# MIPI_Panel.net
KiCad netlist of a schematic drawn in Altium Designer
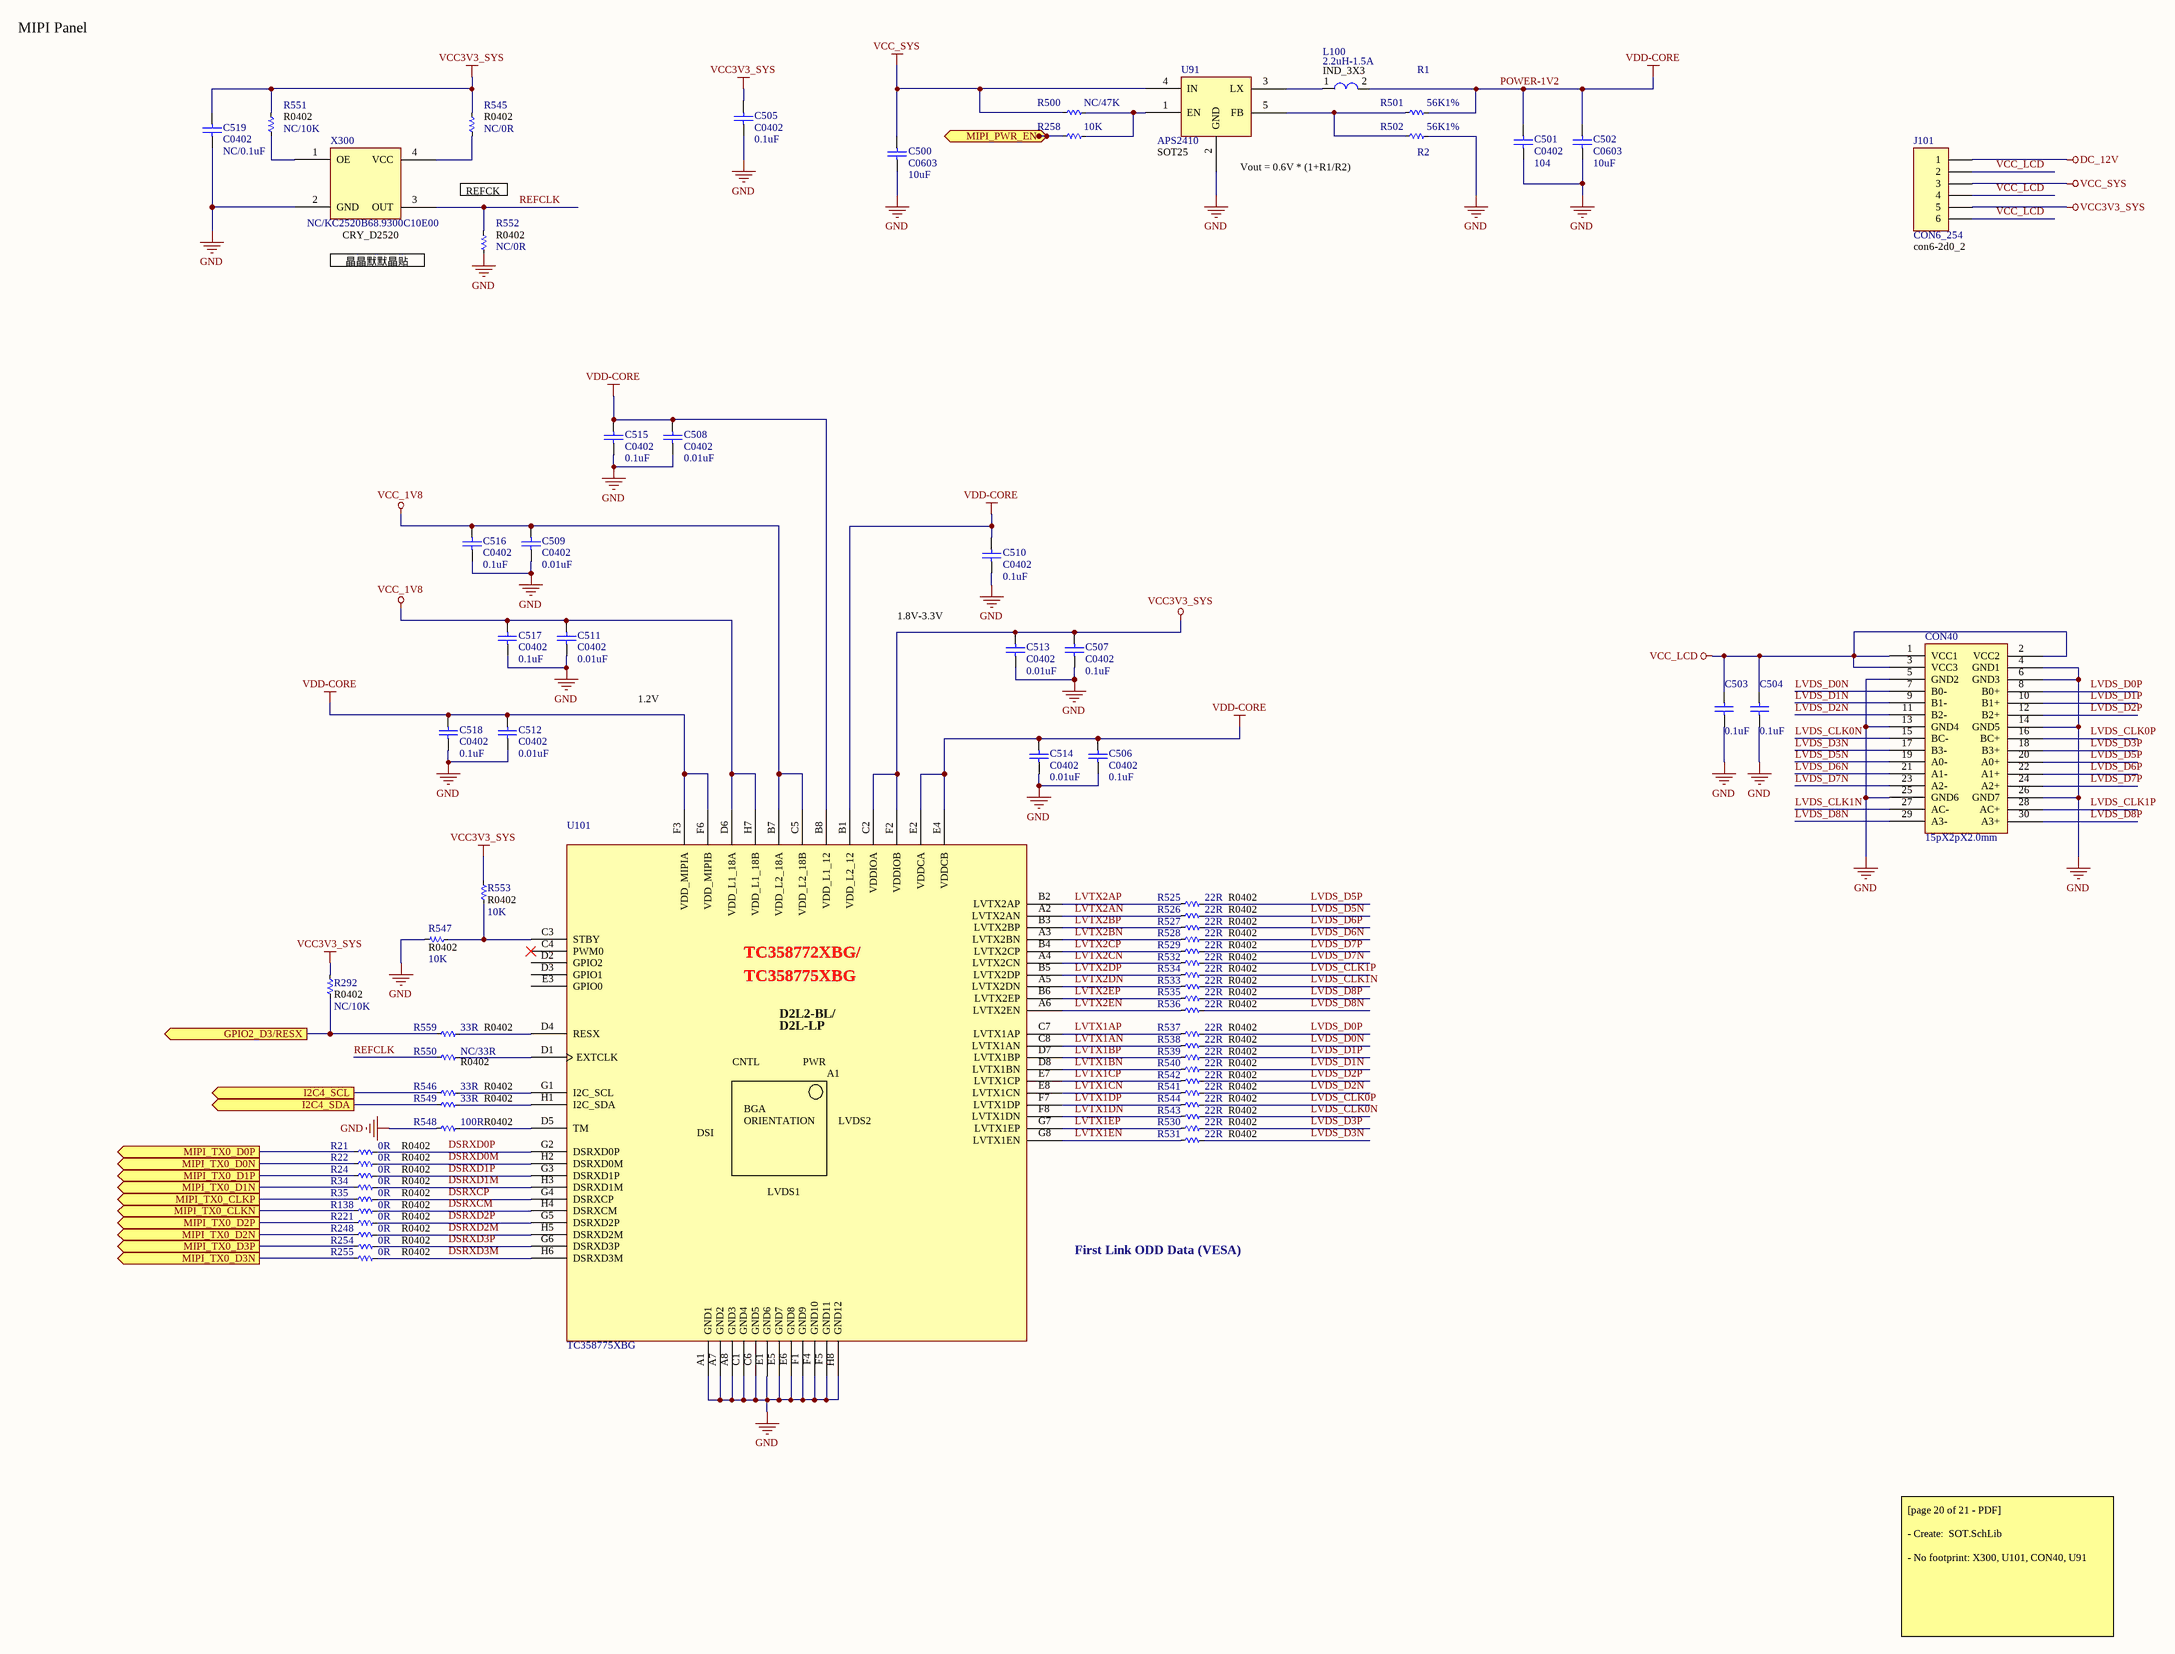
[diagram p0: MIPI_Panel.SchDoc]

(export (version "E")
  (design (tool "Eeschema 10.0.6"))
  (components
    (comp (ref "C500")
      (value "C0603")
      (footprint "C 0603")
      (description "Capacitor")
      (fields (field (name "ALTIUM_VALUE") "10uF") (field (name "PUBLISHER") "Altium Limited"))
      (libsource (lib "Miscellaneous Devices") (part "Cap"))
    )
    (comp (ref "C501")
      (value "C0402")
      (footprint "C 0402")
      (description "Capacitor")
      (fields (field (name "ALTIUM_VALUE") "104") (field (name "PUBLISHER") "Altium Limited"))
      (libsource (lib "Miscellaneous Devices") (part "Cap"))
    )
    (comp (ref "C502")
      (value "C0603")
      (footprint "C 0603")
      (description "Capacitor")
      (fields (field (name "ALTIUM_VALUE") "10uF") (field (name "PUBLISHER") "Altium Limited"))
      (libsource (lib "Miscellaneous Devices") (part "Cap"))
    )
    (comp (ref "C503")
      (value "0.1uF")
      (footprint "C 0402")
      (description "Capacitor")
      (fields (field (name "Comment") "C0402") (field (name "PUBLISHER") "Altium Limited"))
      (libsource (lib "Miscellaneous Devices") (part "Cap"))
    )
    (comp (ref "C504")
      (value "0.1uF")
      (footprint "C 0402")
      (description "Capacitor")
      (fields (field (name "Comment") "C0402") (field (name "PUBLISHER") "Altium Limited"))
      (libsource (lib "Miscellaneous Devices") (part "Cap"))
    )
    (comp (ref "C505")
      (value "C0402")
      (footprint "C 0402")
      (description "Capacitor")
      (fields (field (name "ALTIUM_VALUE") "0.1uF") (field (name "PUBLISHER") "Altium Limited"))
      (libsource (lib "Miscellaneous Devices") (part "Cap"))
    )
    (comp (ref "C506")
      (value "C0402")
      (footprint "C 0402")
      (description "Capacitor")
      (fields (field (name "ALTIUM_VALUE") "0.1uF") (field (name "PUBLISHER") "Altium Limited"))
      (libsource (lib "Miscellaneous Devices") (part "Cap"))
    )
    (comp (ref "C507")
      (value "C0402")
      (footprint "C 0402")
      (description "Capacitor")
      (fields (field (name "ALTIUM_VALUE") "0.1uF") (field (name "PUBLISHER") "Altium Limited"))
      (libsource (lib "Miscellaneous Devices") (part "Cap"))
    )
    (comp (ref "C508")
      (value "C0402")
      (footprint "C 0402")
      (description "Capacitor")
      (fields (field (name "ALTIUM_VALUE") "0.01uF") (field (name "PUBLISHER") "Altium Limited"))
      (libsource (lib "Miscellaneous Devices") (part "Cap"))
    )
    (comp (ref "C509")
      (value "C0402")
      (footprint "C 0402")
      (description "Capacitor")
      (fields (field (name "ALTIUM_VALUE") "0.01uF") (field (name "PUBLISHER") "Altium Limited"))
      (libsource (lib "Miscellaneous Devices") (part "Cap"))
    )
    (comp (ref "C510")
      (value "C0402")
      (footprint "C 0402")
      (description "Capacitor")
      (fields (field (name "ALTIUM_VALUE") "0.1uF") (field (name "PUBLISHER") "Altium Limited"))
      (libsource (lib "Miscellaneous Devices") (part "Cap"))
    )
    (comp (ref "C511")
      (value "C0402")
      (footprint "C 0402")
      (description "Capacitor")
      (fields (field (name "ALTIUM_VALUE") "0.01uF") (field (name "PUBLISHER") "Altium Limited"))
      (libsource (lib "Miscellaneous Devices") (part "Cap"))
    )
    (comp (ref "C512")
      (value "C0402")
      (footprint "C 0402")
      (description "Capacitor")
      (fields (field (name "ALTIUM_VALUE") "0.01uF") (field (name "PUBLISHER") "Altium Limited"))
      (libsource (lib "Miscellaneous Devices") (part "Cap"))
    )
    (comp (ref "C513")
      (value "C0402")
      (footprint "C 0402")
      (description "Capacitor")
      (fields (field (name "ALTIUM_VALUE") "0.01uF") (field (name "PUBLISHER") "Altium Limited"))
      (libsource (lib "Miscellaneous Devices") (part "Cap"))
    )
    (comp (ref "C514")
      (value "C0402")
      (footprint "C 0402")
      (description "Capacitor")
      (fields (field (name "ALTIUM_VALUE") "0.01uF") (field (name "PUBLISHER") "Altium Limited"))
      (libsource (lib "Miscellaneous Devices") (part "Cap"))
    )
    (comp (ref "C515")
      (value "C0402")
      (footprint "C 0402")
      (description "Capacitor")
      (fields (field (name "ALTIUM_VALUE") "0.1uF") (field (name "PUBLISHER") "Altium Limited"))
      (libsource (lib "Miscellaneous Devices") (part "Cap"))
    )
    (comp (ref "C516")
      (value "C0402")
      (footprint "C 0402")
      (description "Capacitor")
      (fields (field (name "ALTIUM_VALUE") "0.1uF") (field (name "PUBLISHER") "Altium Limited"))
      (libsource (lib "Miscellaneous Devices") (part "Cap"))
    )
    (comp (ref "C517")
      (value "C0402")
      (footprint "C 0402")
      (description "Capacitor")
      (fields (field (name "ALTIUM_VALUE") "0.1uF") (field (name "PUBLISHER") "Altium Limited"))
      (libsource (lib "Miscellaneous Devices") (part "Cap"))
    )
    (comp (ref "C518")
      (value "C0402")
      (footprint "C 0402")
      (description "Capacitor")
      (fields (field (name "ALTIUM_VALUE") "0.1uF") (field (name "PUBLISHER") "Altium Limited"))
      (libsource (lib "Miscellaneous Devices") (part "Cap"))
    )
    (comp (ref "C519")
      (value "C0402")
      (footprint "C 0402")
      (description "Capacitor")
      (fields (field (name "ALTIUM_VALUE") "NC/0.1uF") (field (name "PUBLISHER") "Altium Limited"))
      (libsource (lib "Miscellaneous Devices") (part "Cap"))
    )
    (comp (ref "CON40")
      (value "15pX2pX2.0mm")
      (footprint "JP15-D2T")
      (libsource (lib "SOT") (part "15pX2pX2.0mm"))
    )
    (comp (ref "J101")
      (value "CON6_254")
      (footprint "Header6")
      (description "Header, 6-Pin")
      (fields (field (name "ALTIUM_UNNAMED_1") "con6-2d0_2") (field (name "PUBLISHER") "Altium Limited"))
      (libsource (lib "Miscellaneous Connectors") (part "Header 6"))
    )
    (comp (ref "L100")
      (value "2.2uH-1.5A")
      (footprint "L-SMD-M-7.3x4.5")
      (fields
        (field (name "PARTNO") "78477010")
        (field (name "MANUFACTURER") "Wurth Elektronik")
        (field (name "ALTIUM_UNNAMED_1") "IND_3X3")
        (field (name "CREATED BY") "Baojun Chen")
      )
      (libsource (lib "LIBRARY") (part "L-SMD-1"))
    )
    (comp (ref "R21")
      (value "R0402")
      (footprint "R 0402")
      (description "Resistor")
      (fields
        (field (name "MANUFACTURER") "Generic Components")
        (field (name "ALTIUM_VALUE") "0R")
        (field (name "PUBLISHER") "Altium Hobart Technology Centre")
      )
      (libsource (lib "LIBRARY") (part "Res-SMD"))
    )
    (comp (ref "R22")
      (value "R0402")
      (footprint "R 0402")
      (description "Resistor")
      (fields
        (field (name "MANUFACTURER") "Generic Components")
        (field (name "ALTIUM_VALUE") "0R")
        (field (name "PUBLISHER") "Altium Hobart Technology Centre")
      )
      (libsource (lib "LIBRARY") (part "Res-SMD"))
    )
    (comp (ref "R24")
      (value "R0402")
      (footprint "R 0402")
      (description "Resistor")
      (fields
        (field (name "MANUFACTURER") "Generic Components")
        (field (name "ALTIUM_VALUE") "0R")
        (field (name "PUBLISHER") "Altium Hobart Technology Centre")
      )
      (libsource (lib "LIBRARY") (part "Res-SMD"))
    )
    (comp (ref "R34")
      (value "R0402")
      (footprint "R 0402")
      (description "Resistor")
      (fields
        (field (name "MANUFACTURER") "Generic Components")
        (field (name "ALTIUM_VALUE") "0R")
        (field (name "PUBLISHER") "Altium Hobart Technology Centre")
      )
      (libsource (lib "LIBRARY") (part "Res-SMD"))
    )
    (comp (ref "R35")
      (value "R0402")
      (footprint "R 0402")
      (description "Resistor")
      (fields
        (field (name "MANUFACTURER") "Generic Components")
        (field (name "ALTIUM_VALUE") "0R")
        (field (name "PUBLISHER") "Altium Hobart Technology Centre")
      )
      (libsource (lib "LIBRARY") (part "Res-SMD"))
    )
    (comp (ref "R138")
      (value "R0402")
      (footprint "R 0402")
      (description "Resistor")
      (fields
        (field (name "MANUFACTURER") "Generic Components")
        (field (name "ALTIUM_VALUE") "0R")
        (field (name "PUBLISHER") "Altium Hobart Technology Centre")
      )
      (libsource (lib "LIBRARY") (part "Res-SMD"))
    )
    (comp (ref "R221")
      (value "R0402")
      (footprint "R 0402")
      (description "Resistor")
      (fields
        (field (name "MANUFACTURER") "Generic Components")
        (field (name "ALTIUM_VALUE") "0R")
        (field (name "PUBLISHER") "Altium Hobart Technology Centre")
      )
      (libsource (lib "LIBRARY") (part "Res-SMD"))
    )
    (comp (ref "R248")
      (value "R0402")
      (footprint "R 0402")
      (description "Resistor")
      (fields
        (field (name "MANUFACTURER") "Generic Components")
        (field (name "ALTIUM_VALUE") "0R")
        (field (name "PUBLISHER") "Altium Hobart Technology Centre")
      )
      (libsource (lib "LIBRARY") (part "Res-SMD"))
    )
    (comp (ref "R254")
      (value "R0402")
      (footprint "R 0402")
      (description "Resistor")
      (fields
        (field (name "MANUFACTURER") "Generic Components")
        (field (name "ALTIUM_VALUE") "0R")
        (field (name "PUBLISHER") "Altium Hobart Technology Centre")
      )
      (libsource (lib "LIBRARY") (part "Res-SMD"))
    )
    (comp (ref "R255")
      (value "R0402")
      (footprint "R 0402")
      (description "Resistor")
      (fields
        (field (name "MANUFACTURER") "Generic Components")
        (field (name "ALTIUM_VALUE") "0R")
        (field (name "PUBLISHER") "Altium Hobart Technology Centre")
      )
      (libsource (lib "LIBRARY") (part "Res-SMD"))
    )
    (comp (ref "R258")
      (value "10K")
      (footprint "R 0402")
      (description "Resistor")
      (fields
        (field (name "MANUFACTURER") "Generic Components")
        (field (name "Comment") "R0402")
        (field (name "PUBLISHER") "Altium Hobart Technology Centre")
      )
      (libsource (lib "LIBRARY") (part "Res-SMD"))
    )
    (comp (ref "R292")
      (value "R0402")
      (footprint "R 0402")
      (description "Resistor")
      (fields
        (field (name "MANUFACTURER") "Generic Components")
        (field (name "ALTIUM_VALUE") "NC/10K")
        (field (name "PUBLISHER") "Altium Hobart Technology Centre")
      )
      (libsource (lib "LIBRARY") (part "Res-SMD"))
    )
    (comp (ref "R500")
      (value "NC/47K")
      (footprint "R 0402")
      (description "Resistor")
      (fields
        (field (name "MANUFACTURER") "Generic Components")
        (field (name "Comment") "R0402")
        (field (name "PUBLISHER") "Altium Hobart Technology Centre")
      )
      (libsource (lib "LIBRARY") (part "Res-SMD"))
    )
    (comp (ref "R501")
      (value "56K1%")
      (footprint "R 0402")
      (description "Resistor")
      (fields
        (field (name "MANUFACTURER") "Generic Components")
        (field (name "Comment") "R0402")
        (field (name "PUBLISHER") "Altium Hobart Technology Centre")
      )
      (libsource (lib "LIBRARY") (part "Res-SMD"))
    )
    (comp (ref "R502")
      (value "56K1%")
      (footprint "R 0402")
      (description "Resistor")
      (fields
        (field (name "MANUFACTURER") "Generic Components")
        (field (name "Comment") "R0402")
        (field (name "PUBLISHER") "Altium Hobart Technology Centre")
      )
      (libsource (lib "LIBRARY") (part "Res-SMD"))
    )
    (comp (ref "R525")
      (value "R0402")
      (footprint "R 0402")
      (description "Resistor")
      (fields
        (field (name "MANUFACTURER") "Generic Components")
        (field (name "ALTIUM_VALUE") "22R")
        (field (name "PUBLISHER") "Altium Hobart Technology Centre")
      )
      (libsource (lib "LIBRARY") (part "Res-SMD"))
    )
    (comp (ref "R526")
      (value "R0402")
      (footprint "R 0402")
      (description "Resistor")
      (fields
        (field (name "MANUFACTURER") "Generic Components")
        (field (name "ALTIUM_VALUE") "22R")
        (field (name "PUBLISHER") "Altium Hobart Technology Centre")
      )
      (libsource (lib "LIBRARY") (part "Res-SMD"))
    )
    (comp (ref "R527")
      (value "R0402")
      (footprint "R 0402")
      (description "Resistor")
      (fields
        (field (name "MANUFACTURER") "Generic Components")
        (field (name "ALTIUM_VALUE") "22R")
        (field (name "PUBLISHER") "Altium Hobart Technology Centre")
      )
      (libsource (lib "LIBRARY") (part "Res-SMD"))
    )
    (comp (ref "R528")
      (value "R0402")
      (footprint "R 0402")
      (description "Resistor")
      (fields
        (field (name "MANUFACTURER") "Generic Components")
        (field (name "ALTIUM_VALUE") "22R")
        (field (name "PUBLISHER") "Altium Hobart Technology Centre")
      )
      (libsource (lib "LIBRARY") (part "Res-SMD"))
    )
    (comp (ref "R529")
      (value "R0402")
      (footprint "R 0402")
      (description "Resistor")
      (fields
        (field (name "MANUFACTURER") "Generic Components")
        (field (name "ALTIUM_VALUE") "22R")
        (field (name "PUBLISHER") "Altium Hobart Technology Centre")
      )
      (libsource (lib "LIBRARY") (part "Res-SMD"))
    )
    (comp (ref "R530")
      (value "R0402")
      (footprint "R 0402")
      (description "Resistor")
      (fields
        (field (name "MANUFACTURER") "Generic Components")
        (field (name "ALTIUM_VALUE") "22R")
        (field (name "PUBLISHER") "Altium Hobart Technology Centre")
      )
      (libsource (lib "LIBRARY") (part "Res-SMD"))
    )
    (comp (ref "R531")
      (value "R0402")
      (footprint "R 0402")
      (description "Resistor")
      (fields
        (field (name "MANUFACTURER") "Generic Components")
        (field (name "ALTIUM_VALUE") "22R")
        (field (name "PUBLISHER") "Altium Hobart Technology Centre")
      )
      (libsource (lib "LIBRARY") (part "Res-SMD"))
    )
    (comp (ref "R532")
      (value "R0402")
      (footprint "R 0402")
      (description "Resistor")
      (fields
        (field (name "MANUFACTURER") "Generic Components")
        (field (name "ALTIUM_VALUE") "22R")
        (field (name "PUBLISHER") "Altium Hobart Technology Centre")
      )
      (libsource (lib "LIBRARY") (part "Res-SMD"))
    )
    (comp (ref "R533")
      (value "R0402")
      (footprint "R 0402")
      (description "Resistor")
      (fields
        (field (name "MANUFACTURER") "Generic Components")
        (field (name "ALTIUM_VALUE") "22R")
        (field (name "PUBLISHER") "Altium Hobart Technology Centre")
      )
      (libsource (lib "LIBRARY") (part "Res-SMD"))
    )
    (comp (ref "R534")
      (value "R0402")
      (footprint "R 0402")
      (description "Resistor")
      (fields
        (field (name "MANUFACTURER") "Generic Components")
        (field (name "ALTIUM_VALUE") "22R")
        (field (name "PUBLISHER") "Altium Hobart Technology Centre")
      )
      (libsource (lib "LIBRARY") (part "Res-SMD"))
    )
    (comp (ref "R535")
      (value "R0402")
      (footprint "R 0402")
      (description "Resistor")
      (fields
        (field (name "MANUFACTURER") "Generic Components")
        (field (name "ALTIUM_VALUE") "22R")
        (field (name "PUBLISHER") "Altium Hobart Technology Centre")
      )
      (libsource (lib "LIBRARY") (part "Res-SMD"))
    )
    (comp (ref "R536")
      (value "R0402")
      (footprint "R 0402")
      (description "Resistor")
      (fields
        (field (name "MANUFACTURER") "Generic Components")
        (field (name "ALTIUM_VALUE") "22R")
        (field (name "PUBLISHER") "Altium Hobart Technology Centre")
      )
      (libsource (lib "LIBRARY") (part "Res-SMD"))
    )
    (comp (ref "R537")
      (value "R0402")
      (footprint "R 0402")
      (description "Resistor")
      (fields
        (field (name "MANUFACTURER") "Generic Components")
        (field (name "ALTIUM_VALUE") "22R")
        (field (name "PUBLISHER") "Altium Hobart Technology Centre")
      )
      (libsource (lib "LIBRARY") (part "Res-SMD"))
    )
    (comp (ref "R538")
      (value "R0402")
      (footprint "R 0402")
      (description "Resistor")
      (fields
        (field (name "MANUFACTURER") "Generic Components")
        (field (name "ALTIUM_VALUE") "22R")
        (field (name "PUBLISHER") "Altium Hobart Technology Centre")
      )
      (libsource (lib "LIBRARY") (part "Res-SMD"))
    )
    (comp (ref "R539")
      (value "R0402")
      (footprint "R 0402")
      (description "Resistor")
      (fields
        (field (name "MANUFACTURER") "Generic Components")
        (field (name "ALTIUM_VALUE") "22R")
        (field (name "PUBLISHER") "Altium Hobart Technology Centre")
      )
      (libsource (lib "LIBRARY") (part "Res-SMD"))
    )
    (comp (ref "R540")
      (value "R0402")
      (footprint "R 0402")
      (description "Resistor")
      (fields
        (field (name "MANUFACTURER") "Generic Components")
        (field (name "ALTIUM_VALUE") "22R")
        (field (name "PUBLISHER") "Altium Hobart Technology Centre")
      )
      (libsource (lib "LIBRARY") (part "Res-SMD"))
    )
    (comp (ref "R541")
      (value "R0402")
      (footprint "R 0402")
      (description "Resistor")
      (fields
        (field (name "MANUFACTURER") "Generic Components")
        (field (name "ALTIUM_VALUE") "22R")
        (field (name "PUBLISHER") "Altium Hobart Technology Centre")
      )
      (libsource (lib "LIBRARY") (part "Res-SMD"))
    )
    (comp (ref "R542")
      (value "R0402")
      (footprint "R 0402")
      (description "Resistor")
      (fields
        (field (name "MANUFACTURER") "Generic Components")
        (field (name "ALTIUM_VALUE") "22R")
        (field (name "PUBLISHER") "Altium Hobart Technology Centre")
      )
      (libsource (lib "LIBRARY") (part "Res-SMD"))
    )
    (comp (ref "R543")
      (value "R0402")
      (footprint "R 0402")
      (description "Resistor")
      (fields
        (field (name "MANUFACTURER") "Generic Components")
        (field (name "ALTIUM_VALUE") "22R")
        (field (name "PUBLISHER") "Altium Hobart Technology Centre")
      )
      (libsource (lib "LIBRARY") (part "Res-SMD"))
    )
    (comp (ref "R544")
      (value "R0402")
      (footprint "R 0402")
      (description "Resistor")
      (fields
        (field (name "MANUFACTURER") "Generic Components")
        (field (name "ALTIUM_VALUE") "22R")
        (field (name "PUBLISHER") "Altium Hobart Technology Centre")
      )
      (libsource (lib "LIBRARY") (part "Res-SMD"))
    )
    (comp (ref "R545")
      (value "R0402")
      (footprint "R 0402")
      (description "Resistor")
      (fields
        (field (name "MANUFACTURER") "Generic Components")
        (field (name "ALTIUM_VALUE") "NC/0R")
        (field (name "PUBLISHER") "Altium Hobart Technology Centre")
      )
      (libsource (lib "LIBRARY") (part "Res-SMD"))
    )
    (comp (ref "R546")
      (value "R0402")
      (footprint "R 0402")
      (description "Resistor")
      (fields
        (field (name "MANUFACTURER") "Generic Components")
        (field (name "ALTIUM_VALUE") "33R")
        (field (name "PUBLISHER") "Altium Hobart Technology Centre")
      )
      (libsource (lib "LIBRARY") (part "Res-SMD"))
    )
    (comp (ref "R547")
      (value "R0402")
      (footprint "R 0402")
      (description "Resistor")
      (fields
        (field (name "MANUFACTURER") "Generic Components")
        (field (name "ALTIUM_VALUE") "10K")
        (field (name "PUBLISHER") "Altium Hobart Technology Centre")
      )
      (libsource (lib "LIBRARY") (part "Res-SMD"))
    )
    (comp (ref "R548")
      (value "R0402")
      (footprint "R 0402")
      (description "Resistor")
      (fields
        (field (name "MANUFACTURER") "Generic Components")
        (field (name "ALTIUM_VALUE") "100R")
        (field (name "PUBLISHER") "Altium Hobart Technology Centre")
      )
      (libsource (lib "LIBRARY") (part "Res-SMD"))
    )
    (comp (ref "R549")
      (value "R0402")
      (footprint "R 0402")
      (description "Resistor")
      (fields
        (field (name "MANUFACTURER") "Generic Components")
        (field (name "ALTIUM_VALUE") "33R")
        (field (name "PUBLISHER") "Altium Hobart Technology Centre")
      )
      (libsource (lib "LIBRARY") (part "Res-SMD"))
    )
    (comp (ref "R550")
      (value "R0402")
      (footprint "R 0402")
      (description "Resistor")
      (fields
        (field (name "MANUFACTURER") "Generic Components")
        (field (name "ALTIUM_VALUE") "NC/33R")
        (field (name "PUBLISHER") "Altium Hobart Technology Centre")
      )
      (libsource (lib "LIBRARY") (part "Res-SMD"))
    )
    (comp (ref "R551")
      (value "R0402")
      (footprint "R 0402")
      (description "Resistor")
      (fields
        (field (name "MANUFACTURER") "Generic Components")
        (field (name "ALTIUM_VALUE") "NC/10K")
        (field (name "PUBLISHER") "Altium Hobart Technology Centre")
      )
      (libsource (lib "LIBRARY") (part "Res-SMD"))
    )
    (comp (ref "R552")
      (value "R0402")
      (footprint "R 0402")
      (description "Resistor")
      (fields
        (field (name "MANUFACTURER") "Generic Components")
        (field (name "ALTIUM_VALUE") "NC/0R")
        (field (name "PUBLISHER") "Altium Hobart Technology Centre")
      )
      (libsource (lib "LIBRARY") (part "Res-SMD"))
    )
    (comp (ref "R553")
      (value "R0402")
      (footprint "R 0402")
      (description "Resistor")
      (fields
        (field (name "MANUFACTURER") "Generic Components")
        (field (name "ALTIUM_VALUE") "10K")
        (field (name "PUBLISHER") "Altium Hobart Technology Centre")
      )
      (libsource (lib "LIBRARY") (part "Res-SMD"))
    )
    (comp (ref "R559")
      (value "R0402")
      (footprint "R 0402")
      (description "Resistor")
      (fields
        (field (name "MANUFACTURER") "Generic Components")
        (field (name "ALTIUM_VALUE") "33R")
        (field (name "PUBLISHER") "Altium Hobart Technology Centre")
      )
      (libsource (lib "LIBRARY") (part "Res-SMD"))
    )
    (comp (ref "U91")
      (value "APS2410")
      (footprint "SOT-23-5")
      (fields (field (name "PACKAGE") "SOT25"))
      (libsource (lib "SOT") (part "APS2410"))
    )
    (comp (ref "U101")
      (value "TC358775XBG")
      (footprint "BGA-64-TC358774XBG")
      (libsource (lib "SOT") (part "TC358775XBG"))
    )
    (comp (ref "X300")
      (value "NC/KC2520B68.9300C10E00")
      (footprint "Crystal 4-SMD 32x25")
      (libsource (lib "SOT") (part "CRY_D2520"))
    )
  )
  (nets
    (net (code "1") (name "/DSRXCM") (class "Default")
      (node (ref "R138") (pin "1") (pinfunction "1_1") (pintype "passive"))
      (node (ref "U101") (pin "H4") (pinfunction "DSRXCM_H4") (pintype "passive"))
    )
    (net (code "2") (name "/DSRXCP") (class "Default")
      (node (ref "R35") (pin "1") (pinfunction "1_1") (pintype "passive"))
      (node (ref "U101") (pin "G4") (pinfunction "DSRXCP_G4") (pintype "passive"))
    )
    (net (code "3") (name "/DSRXD0M") (class "Default")
      (node (ref "R22") (pin "1") (pinfunction "1_1") (pintype "passive"))
      (node (ref "U101") (pin "H2") (pinfunction "DSRXD0M_H2") (pintype "passive"))
    )
    (net (code "4") (name "/DSRXD0P") (class "Default")
      (node (ref "R21") (pin "1") (pinfunction "1_1") (pintype "passive"))
      (node (ref "U101") (pin "G2") (pinfunction "DSRXD0P_G2") (pintype "passive"))
    )
    (net (code "5") (name "/DSRXD1M") (class "Default")
      (node (ref "R34") (pin "1") (pinfunction "1_1") (pintype "passive"))
      (node (ref "U101") (pin "H3") (pinfunction "DSRXD1M_H3") (pintype "passive"))
    )
    (net (code "6") (name "/DSRXD1P") (class "Default")
      (node (ref "R24") (pin "1") (pinfunction "1_1") (pintype "passive"))
      (node (ref "U101") (pin "G3") (pinfunction "DSRXD1P_G3") (pintype "passive"))
    )
    (net (code "7") (name "/DSRXD2M") (class "Default")
      (node (ref "R248") (pin "1") (pinfunction "1_1") (pintype "passive"))
      (node (ref "U101") (pin "H5") (pinfunction "DSRXD2M_H5") (pintype "passive"))
    )
    (net (code "8") (name "/DSRXD2P") (class "Default")
      (node (ref "R221") (pin "1") (pinfunction "1_1") (pintype "passive"))
      (node (ref "U101") (pin "G5") (pinfunction "DSRXD2P_G5") (pintype "passive"))
    )
    (net (code "9") (name "/DSRXD3M") (class "Default")
      (node (ref "R255") (pin "1") (pinfunction "1_1") (pintype "passive"))
      (node (ref "U101") (pin "H6") (pinfunction "DSRXD3M_H6") (pintype "passive"))
    )
    (net (code "10") (name "/DSRXD3P") (class "Default")
      (node (ref "R254") (pin "1") (pinfunction "1_1") (pintype "passive"))
      (node (ref "U101") (pin "G6") (pinfunction "DSRXD3P_G6") (pintype "passive"))
    )
    (net (code "11") (name "/GPIO2_D3{slash}RESX") (class "Default")
      (node (ref "R292") (pin "2") (pinfunction "2_2") (pintype "passive"))
      (node (ref "R559") (pin "2") (pinfunction "2_2") (pintype "passive"))
    )
    (net (code "12") (name "/I2C4_SCL") (class "Default")
      (node (ref "R546") (pin "2") (pinfunction "2_2") (pintype "passive"))
    )
    (net (code "13") (name "/I2C4_SDA") (class "Default")
      (node (ref "R549") (pin "2") (pinfunction "2_2") (pintype "passive"))
    )
    (net (code "14") (name "/LVDS_CLK0N") (class "Default")
      (node (ref "CON40") (pin "15") (pinfunction "BC-_15") (pintype "passive"))
      (node (ref "R543") (pin "1") (pinfunction "1_1") (pintype "passive"))
    )
    (net (code "15") (name "/LVDS_CLK0P") (class "Default")
      (node (ref "CON40") (pin "16") (pinfunction "BC+_16") (pintype "passive"))
      (node (ref "R544") (pin "1") (pinfunction "1_1") (pintype "passive"))
    )
    (net (code "16") (name "/LVDS_CLK1N") (class "Default")
      (node (ref "CON40") (pin "27") (pinfunction "AC-_27") (pintype "passive"))
      (node (ref "R533") (pin "1") (pinfunction "1_1") (pintype "passive"))
    )
    (net (code "17") (name "/LVDS_CLK1P") (class "Default")
      (node (ref "CON40") (pin "28") (pinfunction "AC+_28") (pintype "passive"))
      (node (ref "R534") (pin "1") (pinfunction "1_1") (pintype "passive"))
    )
    (net (code "18") (name "/LVDS_D0N") (class "Default")
      (node (ref "CON40") (pin "7") (pinfunction "B0-_7") (pintype "passive"))
      (node (ref "R538") (pin "1") (pinfunction "1_1") (pintype "passive"))
    )
    (net (code "19") (name "/LVDS_D0P") (class "Default")
      (node (ref "CON40") (pin "8") (pinfunction "B0+_8") (pintype "passive"))
      (node (ref "R537") (pin "1") (pinfunction "1_1") (pintype "passive"))
    )
    (net (code "20") (name "/LVDS_D1N") (class "Default")
      (node (ref "CON40") (pin "9") (pinfunction "B1-_9") (pintype "passive"))
      (node (ref "R540") (pin "1") (pinfunction "1_1") (pintype "passive"))
    )
    (net (code "21") (name "/LVDS_D1P") (class "Default")
      (node (ref "CON40") (pin "10") (pinfunction "B1+_10") (pintype "passive"))
      (node (ref "R539") (pin "1") (pinfunction "1_1") (pintype "passive"))
    )
    (net (code "22") (name "/LVDS_D2N") (class "Default")
      (node (ref "CON40") (pin "11") (pinfunction "B2-_11") (pintype "passive"))
      (node (ref "R541") (pin "1") (pinfunction "1_1") (pintype "passive"))
    )
    (net (code "23") (name "/LVDS_D2P") (class "Default")
      (node (ref "CON40") (pin "12") (pinfunction "B2+_12") (pintype "passive"))
      (node (ref "R542") (pin "1") (pinfunction "1_1") (pintype "passive"))
    )
    (net (code "24") (name "/LVDS_D3N") (class "Default")
      (node (ref "CON40") (pin "17") (pinfunction "B3-_17") (pintype "passive"))
      (node (ref "R531") (pin "1") (pinfunction "1_1") (pintype "passive"))
    )
    (net (code "25") (name "/LVDS_D3P") (class "Default")
      (node (ref "CON40") (pin "18") (pinfunction "B3+_18") (pintype "passive"))
      (node (ref "R530") (pin "1") (pinfunction "1_1") (pintype "passive"))
    )
    (net (code "26") (name "/LVDS_D5N") (class "Default")
      (node (ref "CON40") (pin "19") (pinfunction "A0-_19") (pintype "passive"))
      (node (ref "R526") (pin "1") (pinfunction "1_1") (pintype "passive"))
    )
    (net (code "27") (name "/LVDS_D5P") (class "Default")
      (node (ref "CON40") (pin "20") (pinfunction "A0+_20") (pintype "passive"))
      (node (ref "R525") (pin "1") (pinfunction "1_1") (pintype "passive"))
    )
    (net (code "28") (name "/LVDS_D6N") (class "Default")
      (node (ref "CON40") (pin "21") (pinfunction "A1-_21") (pintype "passive"))
      (node (ref "R528") (pin "1") (pinfunction "1_1") (pintype "passive"))
    )
    (net (code "29") (name "/LVDS_D6P") (class "Default")
      (node (ref "CON40") (pin "22") (pinfunction "A1+_22") (pintype "passive"))
      (node (ref "R527") (pin "1") (pinfunction "1_1") (pintype "passive"))
    )
    (net (code "30") (name "/LVDS_D7N") (class "Default")
      (node (ref "CON40") (pin "23") (pinfunction "A2-_23") (pintype "passive"))
      (node (ref "R532") (pin "1") (pinfunction "1_1") (pintype "passive"))
    )
    (net (code "31") (name "/LVDS_D7P") (class "Default")
      (node (ref "CON40") (pin "24") (pinfunction "A2+_24") (pintype "passive"))
      (node (ref "R529") (pin "1") (pinfunction "1_1") (pintype "passive"))
    )
    (net (code "32") (name "/LVDS_D8N") (class "Default")
      (node (ref "CON40") (pin "29") (pinfunction "A3-_29") (pintype "passive"))
      (node (ref "R536") (pin "1") (pinfunction "1_1") (pintype "passive"))
    )
    (net (code "33") (name "/LVDS_D8P") (class "Default")
      (node (ref "CON40") (pin "30") (pinfunction "A3+_30") (pintype "passive"))
      (node (ref "R535") (pin "1") (pinfunction "1_1") (pintype "passive"))
    )
    (net (code "34") (name "/LVTX1AN") (class "Default")
      (node (ref "R538") (pin "2") (pinfunction "2_2") (pintype "passive"))
      (node (ref "U101") (pin "C8") (pinfunction "LVTX1AN_C8") (pintype "passive"))
    )
    (net (code "35") (name "/LVTX1AP") (class "Default")
      (node (ref "R537") (pin "2") (pinfunction "2_2") (pintype "passive"))
      (node (ref "U101") (pin "C7") (pinfunction "LVTX1AP_C7") (pintype "passive"))
    )
    (net (code "36") (name "/LVTX1BN") (class "Default")
      (node (ref "R540") (pin "2") (pinfunction "2_2") (pintype "passive"))
      (node (ref "U101") (pin "D8") (pinfunction "LVTX1BN_D8") (pintype "passive"))
    )
    (net (code "37") (name "/LVTX1BP") (class "Default")
      (node (ref "R539") (pin "2") (pinfunction "2_2") (pintype "passive"))
      (node (ref "U101") (pin "D7") (pinfunction "LVTX1BP_D7") (pintype "passive"))
    )
    (net (code "38") (name "/LVTX1CN") (class "Default")
      (node (ref "R541") (pin "2") (pinfunction "2_2") (pintype "passive"))
      (node (ref "U101") (pin "E8") (pinfunction "LVTX1CN_E8") (pintype "passive"))
    )
    (net (code "39") (name "/LVTX1CP") (class "Default")
      (node (ref "R542") (pin "2") (pinfunction "2_2") (pintype "passive"))
      (node (ref "U101") (pin "E7") (pinfunction "LVTX1CP_E7") (pintype "passive"))
    )
    (net (code "40") (name "/LVTX1DN") (class "Default")
      (node (ref "R543") (pin "2") (pinfunction "2_2") (pintype "passive"))
      (node (ref "U101") (pin "F8") (pinfunction "LVTX1DN_F8") (pintype "passive"))
    )
    (net (code "41") (name "/LVTX1DP") (class "Default")
      (node (ref "R544") (pin "2") (pinfunction "2_2") (pintype "passive"))
      (node (ref "U101") (pin "F7") (pinfunction "LVTX1DP_F7") (pintype "passive"))
    )
    (net (code "42") (name "/LVTX1EN") (class "Default")
      (node (ref "R531") (pin "2") (pinfunction "2_2") (pintype "passive"))
      (node (ref "U101") (pin "G8") (pinfunction "LVTX1EN_G8") (pintype "passive"))
    )
    (net (code "43") (name "/LVTX1EP") (class "Default")
      (node (ref "R530") (pin "2") (pinfunction "2_2") (pintype "passive"))
      (node (ref "U101") (pin "G7") (pinfunction "LVTX1EP_G7") (pintype "passive"))
    )
    (net (code "44") (name "/LVTX2AN") (class "Default")
      (node (ref "R526") (pin "2") (pinfunction "2_2") (pintype "passive"))
      (node (ref "U101") (pin "A2") (pinfunction "LVTX2AN_A2") (pintype "passive"))
    )
    (net (code "45") (name "/LVTX2AP") (class "Default")
      (node (ref "R525") (pin "2") (pinfunction "2_2") (pintype "passive"))
      (node (ref "U101") (pin "B2") (pinfunction "LVTX2AP_B2") (pintype "passive"))
    )
    (net (code "46") (name "/LVTX2BN") (class "Default")
      (node (ref "R528") (pin "2") (pinfunction "2_2") (pintype "passive"))
      (node (ref "U101") (pin "A3") (pinfunction "LVTX2BN_A3") (pintype "passive"))
    )
    (net (code "47") (name "/LVTX2BP") (class "Default")
      (node (ref "R527") (pin "2") (pinfunction "2_2") (pintype "passive"))
      (node (ref "U101") (pin "B3") (pinfunction "LVTX2BP_B3") (pintype "passive"))
    )
    (net (code "48") (name "/LVTX2CN") (class "Default")
      (node (ref "R532") (pin "2") (pinfunction "2_2") (pintype "passive"))
      (node (ref "U101") (pin "A4") (pinfunction "LVTX2CN_A4") (pintype "passive"))
    )
    (net (code "49") (name "/LVTX2CP") (class "Default")
      (node (ref "R529") (pin "2") (pinfunction "2_2") (pintype "passive"))
      (node (ref "U101") (pin "B4") (pinfunction "LVTX2CP_B4") (pintype "passive"))
    )
    (net (code "50") (name "/LVTX2DN") (class "Default")
      (node (ref "R533") (pin "2") (pinfunction "2_2") (pintype "passive"))
      (node (ref "U101") (pin "A5") (pinfunction "LVTX2DN_A5") (pintype "passive"))
    )
    (net (code "51") (name "/LVTX2DP") (class "Default")
      (node (ref "R534") (pin "2") (pinfunction "2_2") (pintype "passive"))
      (node (ref "U101") (pin "B5") (pinfunction "LVTX2DP_B5") (pintype "passive"))
    )
    (net (code "52") (name "/LVTX2EN") (class "Default")
      (node (ref "R536") (pin "2") (pinfunction "2_2") (pintype "passive"))
      (node (ref "U101") (pin "A6") (pinfunction "LVTX2EN_A6") (pintype "passive"))
    )
    (net (code "53") (name "/LVTX2EP") (class "Default")
      (node (ref "R535") (pin "2") (pinfunction "2_2") (pintype "passive"))
      (node (ref "U101") (pin "B6") (pinfunction "LVTX2EP_B6") (pintype "passive"))
    )
    (net (code "54") (name "/MIPI_PWR_EN") (class "Default")
      (node (ref "R258") (pin "2") (pinfunction "2_2") (pintype "passive"))
    )
    (net (code "55") (name "/MIPI_TX0_CLKN") (class "Default")
      (node (ref "R138") (pin "2") (pinfunction "2_2") (pintype "passive"))
    )
    (net (code "56") (name "/MIPI_TX0_CLKP") (class "Default")
      (node (ref "R35") (pin "2") (pinfunction "2_2") (pintype "passive"))
    )
    (net (code "57") (name "/MIPI_TX0_D0N") (class "Default")
      (node (ref "R22") (pin "2") (pinfunction "2_2") (pintype "passive"))
    )
    (net (code "58") (name "/MIPI_TX0_D0P") (class "Default")
      (node (ref "R21") (pin "2") (pinfunction "2_2") (pintype "passive"))
    )
    (net (code "59") (name "/MIPI_TX0_D1N") (class "Default")
      (node (ref "R34") (pin "2") (pinfunction "2_2") (pintype "passive"))
    )
    (net (code "60") (name "/MIPI_TX0_D1P") (class "Default")
      (node (ref "R24") (pin "2") (pinfunction "2_2") (pintype "passive"))
    )
    (net (code "61") (name "/MIPI_TX0_D2N") (class "Default")
      (node (ref "R248") (pin "2") (pinfunction "2_2") (pintype "passive"))
    )
    (net (code "62") (name "/MIPI_TX0_D2P") (class "Default")
      (node (ref "R221") (pin "2") (pinfunction "2_2") (pintype "passive"))
    )
    (net (code "63") (name "/MIPI_TX0_D3N") (class "Default")
      (node (ref "R255") (pin "2") (pinfunction "2_2") (pintype "passive"))
    )
    (net (code "64") (name "/MIPI_TX0_D3P") (class "Default")
      (node (ref "R254") (pin "2") (pinfunction "2_2") (pintype "passive"))
    )
    (net (code "65") (name "/REFCLK") (class "Default")
      (node (ref "R550") (pin "2") (pinfunction "2_2") (pintype "passive"))
      (node (ref "R552") (pin "1") (pinfunction "1_1") (pintype "passive"))
      (node (ref "X300") (pin "3") (pinfunction "OUT_3") (pintype "passive"))
    )
    (net (code "66") (name "DC_12V") (class "Default")
      (node (ref "J101") (pin "1") (pinfunction "1_1") (pintype "passive"))
    )
    (net (code "67") (name "GND") (class "Default")
      (node (ref "C500") (pin "2") (pinfunction "2_2") (pintype "passive"))
      (node (ref "C501") (pin "2") (pinfunction "2_2") (pintype "passive"))
      (node (ref "C502") (pin "2") (pinfunction "2_2") (pintype "passive"))
      (node (ref "C503") (pin "2") (pinfunction "2_2") (pintype "passive"))
      (node (ref "C504") (pin "2") (pinfunction "2_2") (pintype "passive"))
      (node (ref "C505") (pin "2") (pinfunction "2_2") (pintype "passive"))
      (node (ref "C506") (pin "2") (pinfunction "2_2") (pintype "passive"))
      (node (ref "C507") (pin "2") (pinfunction "2_2") (pintype "passive"))
      (node (ref "C508") (pin "2") (pinfunction "2_2") (pintype "passive"))
      (node (ref "C509") (pin "2") (pinfunction "2_2") (pintype "passive"))
      (node (ref "C510") (pin "2") (pinfunction "2_2") (pintype "passive"))
      (node (ref "C511") (pin "2") (pinfunction "2_2") (pintype "passive"))
      (node (ref "C512") (pin "2") (pinfunction "2_2") (pintype "passive"))
      (node (ref "C513") (pin "2") (pinfunction "2_2") (pintype "passive"))
      (node (ref "C514") (pin "2") (pinfunction "2_2") (pintype "passive"))
      (node (ref "C515") (pin "2") (pinfunction "2_2") (pintype "passive"))
      (node (ref "C516") (pin "2") (pinfunction "2_2") (pintype "passive"))
      (node (ref "C517") (pin "2") (pinfunction "2_2") (pintype "passive"))
      (node (ref "C518") (pin "2") (pinfunction "2_2") (pintype "passive"))
      (node (ref "C519") (pin "2") (pinfunction "2_2") (pintype "passive"))
      (node (ref "CON40") (pin "13") (pinfunction "GND4_13") (pintype "passive"))
      (node (ref "CON40") (pin "14") (pinfunction "GND5_14") (pintype "passive"))
      (node (ref "CON40") (pin "25") (pinfunction "GND6_25") (pintype "passive"))
      (node (ref "CON40") (pin "26") (pinfunction "GND7_26") (pintype "passive"))
      (node (ref "CON40") (pin "4") (pinfunction "GND1_4") (pintype "passive"))
      (node (ref "CON40") (pin "5") (pinfunction "GND2_5") (pintype "passive"))
      (node (ref "CON40") (pin "6") (pinfunction "GND3_6") (pintype "passive"))
      (node (ref "R502") (pin "1") (pinfunction "1_1") (pintype "passive"))
      (node (ref "R547") (pin "1") (pinfunction "1_1") (pintype "passive"))
      (node (ref "R548") (pin "2") (pinfunction "2_2") (pintype "passive"))
      (node (ref "R552") (pin "2") (pinfunction "2_2") (pintype "passive"))
      (node (ref "U101") (pin "A1") (pinfunction "GND1_A1") (pintype "passive"))
      (node (ref "U101") (pin "A7") (pinfunction "GND2_A7") (pintype "passive"))
      (node (ref "U101") (pin "A8") (pinfunction "GND3_A8") (pintype "passive"))
      (node (ref "U101") (pin "C1") (pinfunction "GND4_C1") (pintype "passive"))
      (node (ref "U101") (pin "C6") (pinfunction "GND5_C6") (pintype "passive"))
      (node (ref "U101") (pin "E1") (pinfunction "GND6_E1") (pintype "passive"))
      (node (ref "U101") (pin "E5") (pinfunction "GND7_E5") (pintype "passive"))
      (node (ref "U101") (pin "E6") (pinfunction "GND8_E6") (pintype "passive"))
      (node (ref "U101") (pin "F1") (pinfunction "GND9_F1") (pintype "passive"))
      (node (ref "U101") (pin "F4") (pinfunction "GND10_F4") (pintype "passive"))
      (node (ref "U101") (pin "F5") (pinfunction "GND11_F5") (pintype "passive"))
      (node (ref "U101") (pin "H8") (pinfunction "GND12_H8") (pintype "passive"))
      (node (ref "U91") (pin "2") (pinfunction "GND_2") (pintype "passive"))
      (node (ref "X300") (pin "2") (pinfunction "GND_2") (pintype "passive"))
    )
    (net (code "68") (name "Net-(U91-EN)") (class "Default")
      (node (ref "R258") (pin "1") (pinfunction "1_1") (pintype "passive"))
      (node (ref "R500") (pin "1") (pinfunction "1_1") (pintype "passive"))
      (node (ref "U91") (pin "1") (pinfunction "EN_1") (pintype "passive"))
    )
    (net (code "69") (name "Net-(U91-FB)") (class "Default")
      (node (ref "R501") (pin "2") (pinfunction "2_2") (pintype "passive"))
      (node (ref "R502") (pin "2") (pinfunction "2_2") (pintype "passive"))
      (node (ref "U91") (pin "5") (pinfunction "FB_5") (pintype "passive"))
    )
    (net (code "70") (name "Net-(U91-LX)") (class "Default")
      (node (ref "L100") (pin "1") (pinfunction "1_1") (pintype "passive"))
      (node (ref "U91") (pin "3") (pinfunction "LX_3") (pintype "passive"))
    )
    (net (code "71") (name "Net-(U101-EXTCLK)") (class "Default")
      (node (ref "R550") (pin "1") (pinfunction "1_1") (pintype "passive"))
      (node (ref "U101") (pin "D1") (pinfunction "EXTCLK_D1") (pintype "passive"))
    )
    (net (code "72") (name "Net-(U101-I2C_SCL)") (class "Default")
      (node (ref "R546") (pin "1") (pinfunction "1_1") (pintype "passive"))
      (node (ref "U101") (pin "G1") (pinfunction "I2C_SCL_G1") (pintype "passive"))
    )
    (net (code "73") (name "Net-(U101-I2C_SDA)") (class "Default")
      (node (ref "R549") (pin "1") (pinfunction "1_1") (pintype "passive"))
      (node (ref "U101") (pin "H1") (pinfunction "I2C_SDA_H1") (pintype "passive"))
    )
    (net (code "74") (name "Net-(U101-RESX)") (class "Default")
      (node (ref "R559") (pin "1") (pinfunction "1_1") (pintype "passive"))
      (node (ref "U101") (pin "D4") (pinfunction "RESX_D4") (pintype "passive"))
    )
    (net (code "75") (name "Net-(U101-STBY)") (class "Default")
      (node (ref "R547") (pin "2") (pinfunction "2_2") (pintype "passive"))
      (node (ref "R553") (pin "1") (pinfunction "1_1") (pintype "passive"))
      (node (ref "U101") (pin "C3") (pinfunction "STBY_C3") (pintype "passive"))
    )
    (net (code "76") (name "Net-(U101-TM)") (class "Default")
      (node (ref "R548") (pin "1") (pinfunction "1_1") (pintype "passive"))
      (node (ref "U101") (pin "D5") (pinfunction "TM_D5") (pintype "passive"))
    )
    (net (code "77") (name "Net-(X300-OE)") (class "Default")
      (node (ref "R551") (pin "2") (pinfunction "2_2") (pintype "passive"))
      (node (ref "X300") (pin "1") (pinfunction "OE_1") (pintype "passive"))
    )
    (net (code "78") (name "Net-(X300-VCC)") (class "Default")
      (node (ref "R545") (pin "2") (pinfunction "2_2") (pintype "passive"))
      (node (ref "X300") (pin "4") (pinfunction "VCC_4") (pintype "passive"))
    )
    (net (code "79") (name "VCC3V3_SYS") (class "Default")
      (node (ref "C505") (pin "1") (pinfunction "1_1") (pintype "passive"))
      (node (ref "C507") (pin "1") (pinfunction "1_1") (pintype "passive"))
      (node (ref "C513") (pin "1") (pinfunction "1_1") (pintype "passive"))
      (node (ref "C519") (pin "1") (pinfunction "1_1") (pintype "passive"))
      (node (ref "J101") (pin "5") (pinfunction "5_5") (pintype "passive"))
      (node (ref "R292") (pin "1") (pinfunction "1_1") (pintype "passive"))
      (node (ref "R545") (pin "1") (pinfunction "1_1") (pintype "passive"))
      (node (ref "R551") (pin "1") (pinfunction "1_1") (pintype "passive"))
      (node (ref "R553") (pin "2") (pinfunction "2_2") (pintype "passive"))
      (node (ref "U101") (pin "C2") (pinfunction "VDDIOA_C2") (pintype "passive"))
      (node (ref "U101") (pin "F2") (pinfunction "VDDIOB_F2") (pintype "passive"))
    )
    (net (code "80") (name "VCC_1V8") (class "Default")
      (node (ref "C509") (pin "1") (pinfunction "1_1") (pintype "passive"))
      (node (ref "C511") (pin "1") (pinfunction "1_1") (pintype "passive"))
      (node (ref "C516") (pin "1") (pinfunction "1_1") (pintype "passive"))
      (node (ref "C517") (pin "1") (pinfunction "1_1") (pintype "passive"))
      (node (ref "U101") (pin "B7") (pinfunction "VDD_L2_18A_B7") (pintype "passive"))
      (node (ref "U101") (pin "C5") (pinfunction "VDD_L2_18B_C5") (pintype "passive"))
      (node (ref "U101") (pin "D6") (pinfunction "VDD_L1_18A_D6") (pintype "passive"))
      (node (ref "U101") (pin "H7") (pinfunction "VDD_L1_18B_H7") (pintype "passive"))
    )
    (net (code "81") (name "VCC_LCD") (class "Default")
      (node (ref "C503") (pin "1") (pinfunction "1_1") (pintype "passive"))
      (node (ref "C504") (pin "1") (pinfunction "1_1") (pintype "passive"))
      (node (ref "CON40") (pin "1") (pinfunction "VCC1_1") (pintype "passive"))
      (node (ref "CON40") (pin "2") (pinfunction "VCC2_2") (pintype "passive"))
      (node (ref "CON40") (pin "3") (pinfunction "VCC3_3") (pintype "passive"))
      (node (ref "J101") (pin "2") (pinfunction "2_2") (pintype "passive"))
      (node (ref "J101") (pin "4") (pinfunction "4_4") (pintype "passive"))
      (node (ref "J101") (pin "6") (pinfunction "6_6") (pintype "passive"))
    )
    (net (code "82") (name "VCC_SYS") (class "Default")
      (node (ref "C500") (pin "1") (pinfunction "1_1") (pintype "passive"))
      (node (ref "J101") (pin "3") (pinfunction "3_3") (pintype "passive"))
      (node (ref "R500") (pin "2") (pinfunction "2_2") (pintype "passive"))
      (node (ref "U91") (pin "4") (pinfunction "IN_4") (pintype "passive"))
    )
    (net (code "83") (name "VDD-CORE") (class "Default")
      (node (ref "C501") (pin "1") (pinfunction "1_1") (pintype "passive"))
      (node (ref "C502") (pin "1") (pinfunction "1_1") (pintype "passive"))
      (node (ref "C506") (pin "1") (pinfunction "1_1") (pintype "passive"))
      (node (ref "C508") (pin "1") (pinfunction "1_1") (pintype "passive"))
      (node (ref "C510") (pin "1") (pinfunction "1_1") (pintype "passive"))
      (node (ref "C512") (pin "1") (pinfunction "1_1") (pintype "passive"))
      (node (ref "C514") (pin "1") (pinfunction "1_1") (pintype "passive"))
      (node (ref "C515") (pin "1") (pinfunction "1_1") (pintype "passive"))
      (node (ref "C518") (pin "1") (pinfunction "1_1") (pintype "passive"))
      (node (ref "L100") (pin "2") (pinfunction "2_2") (pintype "passive"))
      (node (ref "R501") (pin "1") (pinfunction "1_1") (pintype "passive"))
      (node (ref "U101") (pin "B1") (pinfunction "VDD_L2_12_B1") (pintype "passive"))
      (node (ref "U101") (pin "B8") (pinfunction "VDD_L1_12_B8") (pintype "passive"))
      (node (ref "U101") (pin "E2") (pinfunction "VDDCA_E2") (pintype "passive"))
      (node (ref "U101") (pin "E4") (pinfunction "VDDCB_E4") (pintype "passive"))
      (node (ref "U101") (pin "F3") (pinfunction "VDD_MIPIA_F3") (pintype "passive"))
      (node (ref "U101") (pin "F6") (pinfunction "VDD_MIPIB_F6") (pintype "passive"))
    )
    (net (code "84") (name "unconnected-(U101-GPIO0-PadE3)") (class "Default")
      (node (ref "U101") (pin "E3") (pinfunction "GPIO0_E3") (pintype "passive"))
    )
    (net (code "85") (name "unconnected-(U101-GPIO1-PadD3)") (class "Default")
      (node (ref "U101") (pin "D3") (pinfunction "GPIO1_D3") (pintype "passive"))
    )
    (net (code "86") (name "unconnected-(U101-GPIO2-PadD2)") (class "Default")
      (node (ref "U101") (pin "D2") (pinfunction "GPIO2_D2") (pintype "passive"))
    )
    (net (code "87") (name "unconnected-(U101-PWM0-PadC4)") (class "Default")
      (node (ref "U101") (pin "C4") (pinfunction "PWM0_C4") (pintype "passive+no_connect"))
    )
  )
)
